# sch_master.net
KiCad netlist of a schematic drawn in Altium Designer
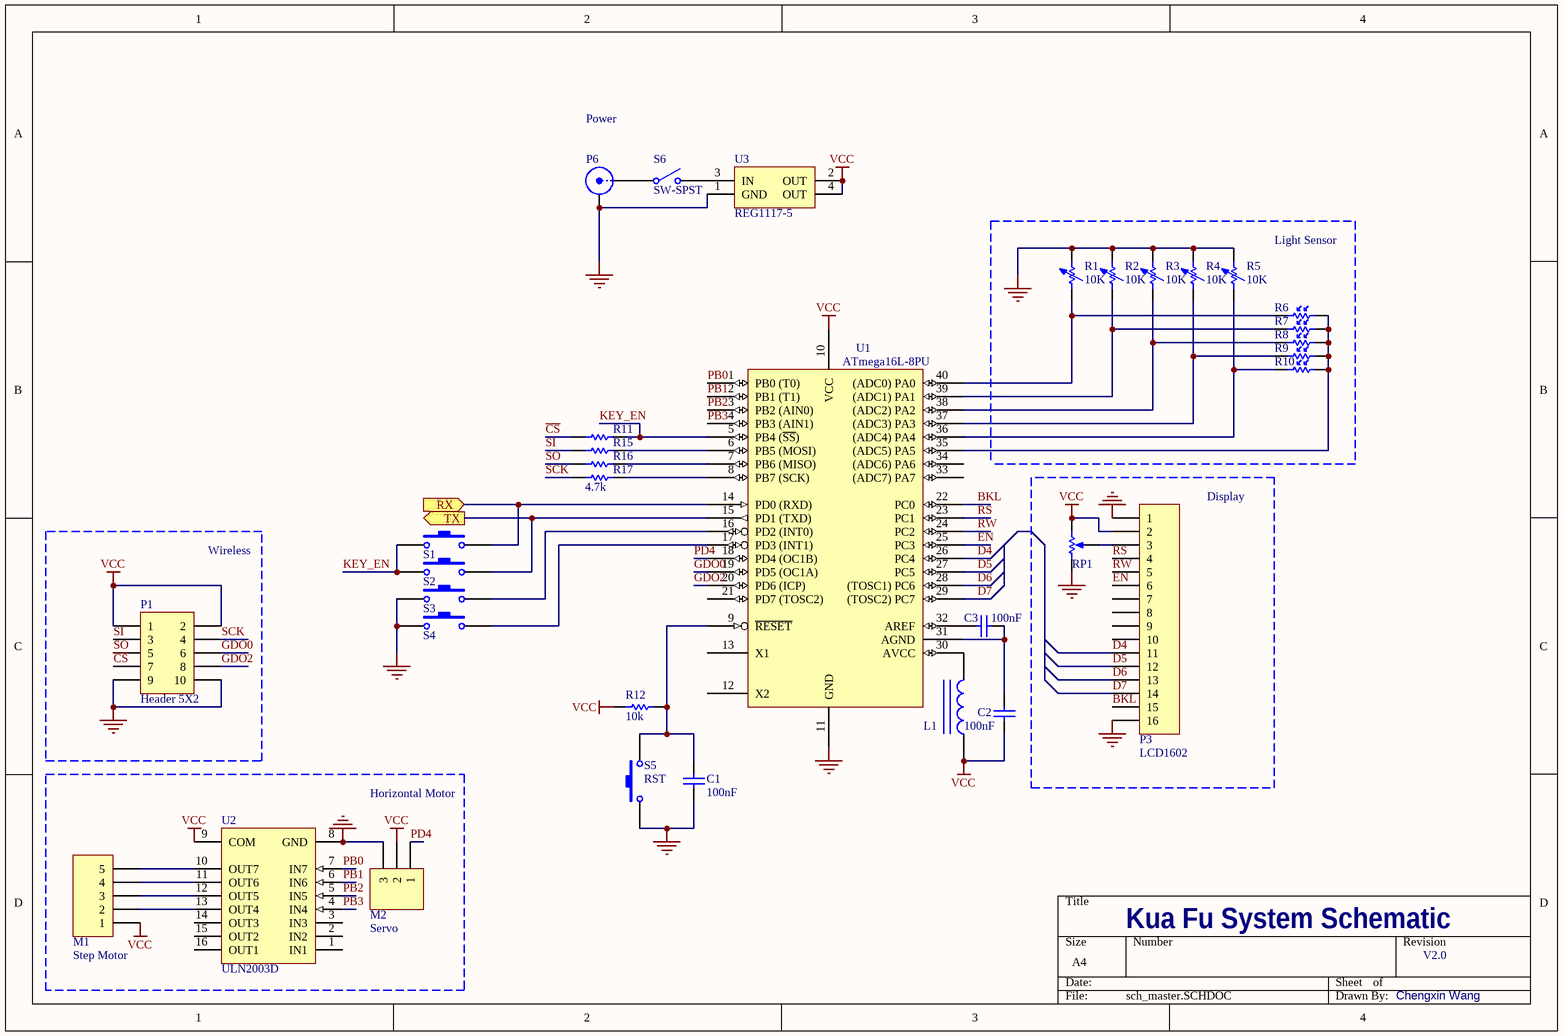
[diagram p0: sch_master.SCHDOC]

(export (version "E")
  (design (tool "Eeschema 10.0.6"))
  (components
    (comp (ref "C1")
      (value "100nF")
      (footprint "RAD-0.3")
      (description "Capacitor")
      (fields (field (name "Comment") "Cap") (field (name "PUBLISHER") "Altium Limited"))
      (libsource (lib "Miscellaneous Devices") (part "Cap"))
    )
    (comp (ref "C2")
      (value "100nF")
      (footprint "RAD-0.3")
      (description "Capacitor")
      (fields (field (name "Comment") "Cap") (field (name "PUBLISHER") "Altium Limited"))
      (libsource (lib "Miscellaneous Devices") (part "Cap"))
    )
    (comp (ref "C3")
      (value "100nF")
      (footprint "RAD-0.3")
      (description "Capacitor")
      (fields (field (name "Comment") "Cap") (field (name "PUBLISHER") "Altium Limited"))
      (libsource (lib "Miscellaneous Devices") (part "Cap"))
    )
    (comp (ref "L1")
      (value "Inductor Iron")
      (footprint "AXIAL-0.9")
      (description "Magnetic-Core Inductor")
      (fields (field (name "PUBLISHER") "Altium Limited"))
      (libsource (lib "Miscellaneous Devices") (part "Inductor Iron"))
    )
    (comp (ref "M1")
      (value "Step Motor")
      (footprint "HDR1X5")
      (description "Header, 5-Pin")
      (fields (field (name "PUBLISHER") "Altium Limited"))
      (libsource (lib "Miscellaneous Connectors") (part "Header 5"))
    )
    (comp (ref "M2")
      (value "Servo")
      (footprint "HDR1X3")
      (description "Header, 3-Pin")
      (fields (field (name "PUBLISHER") "Altium Limited"))
      (libsource (lib "Miscellaneous Connectors") (part "Header 3"))
    )
    (comp (ref "P1")
      (value "Header 5X2")
      (footprint "HDR2X5")
      (description "Header, 5-Pin, Dual row")
      (fields (field (name "PUBLISHER") "Altium Limited"))
      (libsource (lib "Miscellaneous Connectors") (part "Header 5X2"))
    )
    (comp (ref "P3")
      (value "LCD1602")
      (footprint "HDR1X16")
      (description "Header, 16-Pin")
      (fields (field (name "PUBLISHER") "Altium Limited"))
      (libsource (lib "Miscellaneous Connectors") (part "Header 16"))
    )
    (comp (ref "P6")
      (value "SMB")
      (footprint "SMB_V-RJ45")
      (description "SMB Straight Connector")
      (fields (field (name "PUBLISHER") "Altium Limited"))
      (libsource (lib "Miscellaneous Connectors") (part "SMB"))
    )
    (comp (ref "R1")
      (value "10K")
      (footprint "AXIAL-0.7")
      (description "Variable Resistor")
      (fields (field (name "PUBLISHER") "Altium Limited"))
      (libsource (lib "Miscellaneous Devices") (part "Res Adj1"))
    )
    (comp (ref "R2")
      (value "10K")
      (footprint "AXIAL-0.7")
      (description "Variable Resistor")
      (fields (field (name "PUBLISHER") "Altium Limited"))
      (libsource (lib "Miscellaneous Devices") (part "Res Adj1"))
    )
    (comp (ref "R3")
      (value "10K")
      (footprint "AXIAL-0.7")
      (description "Variable Resistor")
      (fields (field (name "PUBLISHER") "Altium Limited"))
      (libsource (lib "Miscellaneous Devices") (part "Res Adj1"))
    )
    (comp (ref "R4")
      (value "10K")
      (footprint "AXIAL-0.7")
      (description "Variable Resistor")
      (fields (field (name "PUBLISHER") "Altium Limited"))
      (libsource (lib "Miscellaneous Devices") (part "Res Adj1"))
    )
    (comp (ref "R5")
      (value "10K")
      (footprint "AXIAL-0.7")
      (description "Variable Resistor")
      (fields (field (name "PUBLISHER") "Altium Limited"))
      (libsource (lib "Miscellaneous Devices") (part "Res Adj1"))
    )
    (comp (ref "R6")
      (value "Res Semi")
      (footprint "AXIAL-0.5")
      (description "Semiconductor Resistor")
      (fields (field (name "PUBLISHER") "Altium Limited"))
      (libsource (lib "Miscellaneous Devices") (part "Res Semi"))
    )
    (comp (ref "R7")
      (value "Res Semi")
      (footprint "AXIAL-0.5")
      (description "Semiconductor Resistor")
      (fields (field (name "PUBLISHER") "Altium Limited"))
      (libsource (lib "Miscellaneous Devices") (part "Res Semi"))
    )
    (comp (ref "R8")
      (value "Res Semi")
      (footprint "AXIAL-0.5")
      (description "Semiconductor Resistor")
      (fields (field (name "PUBLISHER") "Altium Limited"))
      (libsource (lib "Miscellaneous Devices") (part "Res Semi"))
    )
    (comp (ref "R9")
      (value "Res Semi")
      (footprint "AXIAL-0.5")
      (description "Semiconductor Resistor")
      (fields (field (name "PUBLISHER") "Altium Limited"))
      (libsource (lib "Miscellaneous Devices") (part "Res Semi"))
    )
    (comp (ref "R10")
      (value "Res Semi")
      (footprint "AXIAL-0.5")
      (description "Semiconductor Resistor")
      (fields (field (name "PUBLISHER") "Altium Limited"))
      (libsource (lib "Miscellaneous Devices") (part "Res Semi"))
    )
    (comp (ref "R11")
      (value "Res1")
      (footprint "AXIAL-0.3")
      (description "Resistor")
      (fields (field (name "PUBLISHER") "Altium Limited"))
      (libsource (lib "Miscellaneous Devices") (part "Res1"))
    )
    (comp (ref "R12")
      (value "10k")
      (footprint "AXIAL-0.3")
      (description "Resistor")
      (fields (field (name "Comment") "Res1") (field (name "PUBLISHER") "Altium Limited"))
      (libsource (lib "Miscellaneous Devices") (part "Res1"))
    )
    (comp (ref "R15")
      (value "Res1")
      (footprint "AXIAL-0.3")
      (description "Resistor")
      (fields (field (name "PUBLISHER") "Altium Limited"))
      (libsource (lib "Miscellaneous Devices") (part "Res1"))
    )
    (comp (ref "R16")
      (value "Res1")
      (footprint "AXIAL-0.3")
      (description "Resistor")
      (fields (field (name "PUBLISHER") "Altium Limited"))
      (libsource (lib "Miscellaneous Devices") (part "Res1"))
    )
    (comp (ref "R17")
      (value "4.7k")
      (footprint "AXIAL-0.3")
      (description "Resistor")
      (fields (field (name "Comment") "Res1") (field (name "PUBLISHER") "Altium Limited"))
      (libsource (lib "Miscellaneous Devices") (part "Res1"))
    )
    (comp (ref "RP1")
      (value "RPot")
      (footprint "VR5")
      (description "Potentiometer")
      (fields (field (name "PUBLISHER") "Altium Limited"))
      (libsource (lib "Miscellaneous Devices") (part "RPot"))
    )
    (comp (ref "S1")
      (value "SW-PB")
      (footprint "SPST-2")
      (description "Switch")
      (fields (field (name "PUBLISHER") "Altium Limited"))
      (libsource (lib "Miscellaneous Devices") (part "SW-PB"))
    )
    (comp (ref "S2")
      (value "SW-PB")
      (footprint "SPST-2")
      (description "Switch")
      (fields (field (name "PUBLISHER") "Altium Limited"))
      (libsource (lib "Miscellaneous Devices") (part "SW-PB"))
    )
    (comp (ref "S3")
      (value "SW-PB")
      (footprint "SPST-2")
      (description "Switch")
      (fields (field (name "PUBLISHER") "Altium Limited"))
      (libsource (lib "Miscellaneous Devices") (part "SW-PB"))
    )
    (comp (ref "S4")
      (value "SW-PB")
      (footprint "SPST-2")
      (description "Switch")
      (fields (field (name "PUBLISHER") "Altium Limited"))
      (libsource (lib "Miscellaneous Devices") (part "SW-PB"))
    )
    (comp (ref "S5")
      (value "RST")
      (footprint "SPST-2")
      (description "Switch")
      (fields (field (name "PUBLISHER") "Altium Limited"))
      (libsource (lib "Miscellaneous Devices") (part "SW-PB"))
    )
    (comp (ref "S6")
      (value "SW-SPST")
      (footprint "SPST-2")
      (description "Single-Pole, Single-Throw Switch")
      (fields (field (name "PUBLISHER") "Altium Limited"))
      (libsource (lib "Miscellaneous Devices") (part "SW-SPST"))
    )
    (comp (ref "U1")
      (value "ATmega16L-8PU")
      (footprint "DIP-40")
      (description "Atmel Microcontroller - Library created by carel..  <www.mpfreezone.com>")
      (libsource (lib "avr_protel") (part "ATMEGA16_DIP40"))
    )
    (comp (ref "U2")
      (value "ULN2003D")
      (footprint "SO16")
      (description "Seven Darlington Array")
      (fields (field (name "PUBLISHER") "Altium Limited"))
      (libsource (lib "ST Interface Darlington Driver") (part "ULN2003D"))
    )
    (comp (ref "U3")
      (value "REG1117-5")
      (footprint "ZZ311")
      (description "800mA and 1A Low Dropout Positive Regulator 2.85V, 3.3V, 5V, and Adjustable")
      (fields (field (name "PUBLISHER") "Altium Limited"))
      (libsource (lib "BB Power Mgt Voltage Regulator") (part "REG1117-5"))
    )
  )
  (nets
    (net (code "1") (name "/BKL") (class "Default")
      (node (ref "P3") (pin "15") (pinfunction "15_15") (pintype "passive"))
      (node (ref "U1") (pin "22") (pinfunction "PC0_22") (pintype "bidirectional"))
    )
    (net (code "2") (name "/D4") (class "Default")
      (node (ref "P3") (pin "11") (pinfunction "11_11") (pintype "passive"))
      (node (ref "U1") (pin "26") (pinfunction "PC4_26") (pintype "bidirectional"))
    )
    (net (code "3") (name "/D5") (class "Default")
      (node (ref "P3") (pin "12") (pinfunction "12_12") (pintype "passive"))
      (node (ref "U1") (pin "27") (pinfunction "PC5_27") (pintype "bidirectional"))
    )
    (net (code "4") (name "/D6") (class "Default")
      (node (ref "P3") (pin "13") (pinfunction "13_13") (pintype "passive"))
      (node (ref "U1") (pin "28") (pinfunction "(TOSC1)_PC6_28") (pintype "bidirectional"))
    )
    (net (code "5") (name "/D7") (class "Default")
      (node (ref "P3") (pin "14") (pinfunction "14_14") (pintype "passive"))
      (node (ref "U1") (pin "29") (pinfunction "(TOSC2)_PC7_29") (pintype "bidirectional"))
    )
    (net (code "6") (name "/EN") (class "Default")
      (node (ref "P3") (pin "6") (pinfunction "6_6") (pintype "passive"))
      (node (ref "U1") (pin "25") (pinfunction "PC3_25") (pintype "bidirectional"))
    )
    (net (code "7") (name "/GDO0") (class "Default")
      (node (ref "P1") (pin "6") (pinfunction "6_6") (pintype "passive"))
      (node (ref "U1") (pin "19") (pinfunction "PD5_(OC1A)_19") (pintype "bidirectional"))
    )
    (net (code "8") (name "/GDO2") (class "Default")
      (node (ref "P1") (pin "8") (pinfunction "8_8") (pintype "passive"))
      (node (ref "U1") (pin "20") (pinfunction "PD6_(ICP)_20") (pintype "bidirectional"))
    )
    (net (code "9") (name "/KEY_EN") (class "Default")
      (node (ref "R11") (pin "2") (pinfunction "2_2") (pintype "passive"))
      (node (ref "S1") (pin "1") (pinfunction "1_1") (pintype "passive"))
      (node (ref "S2") (pin "1") (pinfunction "1_1") (pintype "passive"))
      (node (ref "U1") (pin "5") (pinfunction "PB4_(~{SS})_5") (pintype "bidirectional"))
    )
    (net (code "10") (name "/PB0") (class "Default")
      (node (ref "U1") (pin "1") (pinfunction "PB0_(T0)_1") (pintype "bidirectional"))
      (node (ref "U2") (pin "7") (pinfunction "IN7_7") (pintype "input"))
    )
    (net (code "11") (name "/PB1") (class "Default")
      (node (ref "U1") (pin "2") (pinfunction "PB1_(T1)_2") (pintype "bidirectional"))
      (node (ref "U2") (pin "6") (pinfunction "IN6_6") (pintype "input"))
    )
    (net (code "12") (name "/PB2") (class "Default")
      (node (ref "U1") (pin "3") (pinfunction "PB2_(AIN0)_3") (pintype "bidirectional"))
      (node (ref "U2") (pin "5") (pinfunction "IN5_5") (pintype "input"))
    )
    (net (code "13") (name "/PB3") (class "Default")
      (node (ref "U1") (pin "4") (pinfunction "PB3_(AIN1)_4") (pintype "bidirectional"))
      (node (ref "U2") (pin "4") (pinfunction "IN4_4") (pintype "input"))
    )
    (net (code "14") (name "/PD4") (class "Default")
      (node (ref "M2") (pin "1") (pinfunction "1_1") (pintype "passive"))
      (node (ref "U1") (pin "18") (pinfunction "PD4_(OC1B)_18") (pintype "bidirectional"))
    )
    (net (code "15") (name "/RS") (class "Default")
      (node (ref "P3") (pin "4") (pinfunction "4_4") (pintype "passive"))
      (node (ref "U1") (pin "23") (pinfunction "PC1_23") (pintype "bidirectional"))
    )
    (net (code "16") (name "/RW") (class "Default")
      (node (ref "P3") (pin "5") (pinfunction "5_5") (pintype "passive"))
      (node (ref "U1") (pin "24") (pinfunction "PC2_24") (pintype "bidirectional"))
    )
    (net (code "17") (name "/RX") (class "Default")
      (node (ref "S1") (pin "2") (pinfunction "2_2") (pintype "passive"))
      (node (ref "U1") (pin "14") (pinfunction "PD0_(RXD)_14") (pintype "input"))
    )
    (net (code "18") (name "/SCK") (class "Default")
      (node (ref "P1") (pin "4") (pinfunction "4_4") (pintype "passive"))
      (node (ref "R17") (pin "1") (pinfunction "1_1") (pintype "passive"))
    )
    (net (code "19") (name "/SI") (class "Default")
      (node (ref "P1") (pin "3") (pinfunction "3_3") (pintype "passive"))
      (node (ref "R15") (pin "1") (pinfunction "1_1") (pintype "passive"))
    )
    (net (code "20") (name "/SO") (class "Default")
      (node (ref "P1") (pin "5") (pinfunction "5_5") (pintype "passive"))
      (node (ref "R16") (pin "1") (pinfunction "1_1") (pintype "passive"))
    )
    (net (code "21") (name "/TX") (class "Default")
      (node (ref "S2") (pin "2") (pinfunction "2_2") (pintype "passive"))
      (node (ref "U1") (pin "15") (pinfunction "PD1_(TXD)_15") (pintype "output"))
    )
    (net (code "22") (name "/~{CS}") (class "Default")
      (node (ref "P1") (pin "7") (pinfunction "7_7") (pintype "passive"))
      (node (ref "R11") (pin "1") (pinfunction "1_1") (pintype "passive"))
    )
    (net (code "23") (name "GND") (class "Default")
      (node (ref "C1") (pin "1") (pinfunction "1_1") (pintype "passive"))
      (node (ref "M2") (pin "3") (pinfunction "3_3") (pintype "passive"))
      (node (ref "P1") (pin "10") (pinfunction "10_10") (pintype "passive"))
      (node (ref "P1") (pin "9") (pinfunction "9_9") (pintype "passive"))
      (node (ref "P3") (pin "1") (pinfunction "1_1") (pintype "passive"))
      (node (ref "P3") (pin "16") (pinfunction "16_16") (pintype "passive"))
      (node (ref "P6") (pin "2") (pinfunction "Y_2") (pintype "passive"))
      (node (ref "R1") (pin "2") (pinfunction "2_2") (pintype "passive"))
      (node (ref "R2") (pin "2") (pinfunction "2_2") (pintype "passive"))
      (node (ref "R3") (pin "2") (pinfunction "2_2") (pintype "passive"))
      (node (ref "R4") (pin "2") (pinfunction "2_2") (pintype "passive"))
      (node (ref "R5") (pin "2") (pinfunction "2_2") (pintype "passive"))
      (node (ref "RP1") (pin "1") (pinfunction "TOP_1") (pintype "passive"))
      (node (ref "S3") (pin "1") (pinfunction "1_1") (pintype "passive"))
      (node (ref "S4") (pin "1") (pinfunction "1_1") (pintype "passive"))
      (node (ref "S5") (pin "1") (pinfunction "1_1") (pintype "passive"))
      (node (ref "U1") (pin "11") (pinfunction "GND_11") (pintype "power_in"))
      (node (ref "U2") (pin "8") (pinfunction "GND_8") (pintype "power_in"))
      (node (ref "U3") (pin "1") (pinfunction "GND_1") (pintype "power_in"))
    )
    (net (code "24") (name "Net-(P6-X)") (class "Default")
      (node (ref "P6") (pin "1") (pinfunction "X_1") (pintype "passive"))
      (node (ref "S6") (pin "1") (pinfunction "COMMON_1") (pintype "passive"))
    )
    (net (code "25") (name "Net-(RP1-TAP)") (class "Default")
      (node (ref "P3") (pin "3") (pinfunction "3_3") (pintype "passive"))
      (node (ref "RP1") (pin "3") (pinfunction "TAP_3") (pintype "passive"))
    )
    (net (code "26") (name "Net-(S6-NO)") (class "Default")
      (node (ref "S6") (pin "2") (pinfunction "NO_2") (pintype "passive"))
      (node (ref "U3") (pin "3") (pinfunction "IN_3") (pintype "power_in"))
    )
    (net (code "27") (name "Net-(U1-(ADC0)_PA0)") (class "Default")
      (node (ref "R1") (pin "1") (pinfunction "1_1") (pintype "passive"))
      (node (ref "R6") (pin "1") (pinfunction "1_1") (pintype "passive"))
      (node (ref "U1") (pin "40") (pinfunction "(ADC0)_PA0_40") (pintype "bidirectional"))
    )
    (net (code "28") (name "Net-(U1-(ADC1)_PA1)") (class "Default")
      (node (ref "R2") (pin "1") (pinfunction "1_1") (pintype "passive"))
      (node (ref "R7") (pin "1") (pinfunction "1_1") (pintype "passive"))
      (node (ref "U1") (pin "39") (pinfunction "(ADC1)_PA1_39") (pintype "bidirectional"))
    )
    (net (code "29") (name "Net-(U1-(ADC2)_PA2)") (class "Default")
      (node (ref "R3") (pin "1") (pinfunction "1_1") (pintype "passive"))
      (node (ref "R8") (pin "1") (pinfunction "1_1") (pintype "passive"))
      (node (ref "U1") (pin "38") (pinfunction "(ADC2)_PA2_38") (pintype "bidirectional"))
    )
    (net (code "30") (name "Net-(U1-(ADC3)_PA3)") (class "Default")
      (node (ref "R4") (pin "1") (pinfunction "1_1") (pintype "passive"))
      (node (ref "R9") (pin "1") (pinfunction "1_1") (pintype "passive"))
      (node (ref "U1") (pin "37") (pinfunction "(ADC3)_PA3_37") (pintype "bidirectional"))
    )
    (net (code "31") (name "Net-(U1-(ADC4)_PA4)") (class "Default")
      (node (ref "R10") (pin "1") (pinfunction "1_1") (pintype "passive"))
      (node (ref "R5") (pin "1") (pinfunction "1_1") (pintype "passive"))
      (node (ref "U1") (pin "36") (pinfunction "(ADC4)_PA4_36") (pintype "bidirectional"))
    )
    (net (code "32") (name "Net-(U1-(ADC5)_PA5)") (class "Default")
      (node (ref "R10") (pin "2") (pinfunction "2_2") (pintype "passive"))
      (node (ref "R6") (pin "2") (pinfunction "2_2") (pintype "passive"))
      (node (ref "R7") (pin "2") (pinfunction "2_2") (pintype "passive"))
      (node (ref "R8") (pin "2") (pinfunction "2_2") (pintype "passive"))
      (node (ref "R9") (pin "2") (pinfunction "2_2") (pintype "passive"))
      (node (ref "U1") (pin "35") (pinfunction "(ADC5)_PA5_35") (pintype "bidirectional"))
    )
    (net (code "33") (name "Net-(U1-AGND)") (class "Default")
      (node (ref "C2") (pin "2") (pinfunction "2_2") (pintype "passive"))
      (node (ref "C3") (pin "2") (pinfunction "2_2") (pintype "passive"))
      (node (ref "U1") (pin "31") (pinfunction "AGND_31") (pintype "power_in"))
    )
    (net (code "34") (name "Net-(U1-AREF)") (class "Default")
      (node (ref "C3") (pin "1") (pinfunction "1_1") (pintype "passive"))
      (node (ref "U1") (pin "32") (pinfunction "AREF_32") (pintype "bidirectional"))
    )
    (net (code "35") (name "Net-(U1-AVCC)") (class "Default")
      (node (ref "L1") (pin "2") (pinfunction "2_2") (pintype "passive"))
      (node (ref "U1") (pin "30") (pinfunction "AVCC_30") (pintype "bidirectional"))
    )
    (net (code "36") (name "Net-(U1-PB5_(MOSI))") (class "Default")
      (node (ref "R15") (pin "2") (pinfunction "2_2") (pintype "passive"))
      (node (ref "U1") (pin "6") (pinfunction "PB5_(MOSI)_6") (pintype "bidirectional"))
    )
    (net (code "37") (name "Net-(U1-PB6_(MISO))") (class "Default")
      (node (ref "R16") (pin "2") (pinfunction "2_2") (pintype "passive"))
      (node (ref "U1") (pin "7") (pinfunction "PB6_(MISO)_7") (pintype "bidirectional"))
    )
    (net (code "38") (name "Net-(U1-PB7_(SCK))") (class "Default")
      (node (ref "R17") (pin "2") (pinfunction "2_2") (pintype "passive"))
      (node (ref "U1") (pin "8") (pinfunction "PB7_(SCK)_8") (pintype "bidirectional"))
    )
    (net (code "39") (name "Net-(U1-PD2_(INT0))") (class "Default")
      (node (ref "S3") (pin "2") (pinfunction "2_2") (pintype "passive"))
      (node (ref "U1") (pin "16") (pinfunction "PD2_(INT0)_16") (pintype "bidirectional"))
    )
    (net (code "40") (name "Net-(U1-PD3_(INT1))") (class "Default")
      (node (ref "S4") (pin "2") (pinfunction "2_2") (pintype "passive"))
      (node (ref "U1") (pin "17") (pinfunction "PD3_(INT1)_17") (pintype "bidirectional"))
    )
    (net (code "41") (name "Net-(U1-RESET)") (class "Default")
      (node (ref "C1") (pin "2") (pinfunction "2_2") (pintype "passive"))
      (node (ref "R12") (pin "2") (pinfunction "2_2") (pintype "passive"))
      (node (ref "S5") (pin "2") (pinfunction "2_2") (pintype "passive"))
      (node (ref "U1") (pin "9") (pinfunction "RESET_9") (pintype "input"))
    )
    (net (code "42") (name "Net-(U2-OUT4)") (class "Default")
      (node (ref "M1") (pin "2") (pinfunction "2_2") (pintype "passive"))
      (node (ref "U2") (pin "13") (pinfunction "OUT4_13") (pintype "open_collector"))
    )
    (net (code "43") (name "Net-(U2-OUT5)") (class "Default")
      (node (ref "M1") (pin "3") (pinfunction "3_3") (pintype "passive"))
      (node (ref "U2") (pin "12") (pinfunction "OUT5_12") (pintype "open_collector"))
    )
    (net (code "44") (name "Net-(U2-OUT6)") (class "Default")
      (node (ref "M1") (pin "4") (pinfunction "4_4") (pintype "passive"))
      (node (ref "U2") (pin "11") (pinfunction "OUT6_11") (pintype "open_collector"))
    )
    (net (code "45") (name "Net-(U2-OUT7)") (class "Default")
      (node (ref "M1") (pin "5") (pinfunction "5_5") (pintype "passive"))
      (node (ref "U2") (pin "10") (pinfunction "OUT7_10") (pintype "open_collector"))
    )
    (net (code "46") (name "VCC") (class "Default")
      (node (ref "C2") (pin "1") (pinfunction "1_1") (pintype "passive"))
      (node (ref "L1") (pin "1") (pinfunction "1_1") (pintype "passive"))
      (node (ref "M1") (pin "1") (pinfunction "1_1") (pintype "passive"))
      (node (ref "M2") (pin "2") (pinfunction "2_2") (pintype "passive"))
      (node (ref "P1") (pin "1") (pinfunction "1_1") (pintype "passive"))
      (node (ref "P1") (pin "2") (pinfunction "2_2") (pintype "passive"))
      (node (ref "P3") (pin "2") (pinfunction "2_2") (pintype "passive"))
      (node (ref "R12") (pin "1") (pinfunction "1_1") (pintype "passive"))
      (node (ref "RP1") (pin "2") (pinfunction "BOT_2") (pintype "passive"))
      (node (ref "U1") (pin "10") (pinfunction "VCC_10") (pintype "power_in"))
      (node (ref "U2") (pin "9") (pinfunction "COM_9") (pintype "passive"))
      (node (ref "U3") (pin "2") (pinfunction "OUT_2") (pintype "power_in"))
      (node (ref "U3") (pin "4") (pinfunction "OUT_4") (pintype "power_in"))
    )
    (net (code "47") (name "unconnected-(P3-Pad7)") (class "Default")
      (node (ref "P3") (pin "7") (pinfunction "7_7") (pintype "passive"))
    )
    (net (code "48") (name "unconnected-(P3-Pad8)") (class "Default")
      (node (ref "P3") (pin "8") (pinfunction "8_8") (pintype "passive"))
    )
    (net (code "49") (name "unconnected-(P3-Pad9)") (class "Default")
      (node (ref "P3") (pin "9") (pinfunction "9_9") (pintype "passive"))
    )
    (net (code "50") (name "unconnected-(P3-Pad10)") (class "Default")
      (node (ref "P3") (pin "10") (pinfunction "10_10") (pintype "passive"))
    )
    (net (code "51") (name "unconnected-(U1-(ADC6)_PA6-Pad34)") (class "Default")
      (node (ref "U1") (pin "34") (pinfunction "(ADC6)_PA6_34") (pintype "bidirectional"))
    )
    (net (code "52") (name "unconnected-(U1-(ADC7)_PA7-Pad33)") (class "Default")
      (node (ref "U1") (pin "33") (pinfunction "(ADC7)_PA7_33") (pintype "bidirectional"))
    )
    (net (code "53") (name "unconnected-(U1-PD7_(TOSC2)-Pad21)") (class "Default")
      (node (ref "U1") (pin "21") (pinfunction "PD7_(TOSC2)_21") (pintype "bidirectional"))
    )
    (net (code "54") (name "unconnected-(U1-X1-Pad13)") (class "Default")
      (node (ref "U1") (pin "13") (pinfunction "X1_13") (pintype "tri_state"))
    )
    (net (code "55") (name "unconnected-(U1-X2-Pad12)") (class "Default")
      (node (ref "U1") (pin "12") (pinfunction "X2_12") (pintype "tri_state"))
    )
    (net (code "56") (name "unconnected-(U2-IN1-Pad1)") (class "Default")
      (node (ref "U2") (pin "1") (pinfunction "IN1_1") (pintype "open_collector"))
    )
    (net (code "57") (name "unconnected-(U2-IN2-Pad2)") (class "Default")
      (node (ref "U2") (pin "2") (pinfunction "IN2_2") (pintype "open_collector"))
    )
    (net (code "58") (name "unconnected-(U2-IN3-Pad3)") (class "Default")
      (node (ref "U2") (pin "3") (pinfunction "IN3_3") (pintype "open_collector"))
    )
    (net (code "59") (name "unconnected-(U2-OUT1-Pad16)") (class "Default")
      (node (ref "U2") (pin "16") (pinfunction "OUT1_16") (pintype "open_collector"))
    )
    (net (code "60") (name "unconnected-(U2-OUT2-Pad15)") (class "Default")
      (node (ref "U2") (pin "15") (pinfunction "OUT2_15") (pintype "open_collector"))
    )
    (net (code "61") (name "unconnected-(U2-OUT3-Pad14)") (class "Default")
      (node (ref "U2") (pin "14") (pinfunction "OUT3_14") (pintype "open_collector"))
    )
  )
)
